# TinyUART.net
KiCad netlist of a schematic drawn in EAGLE
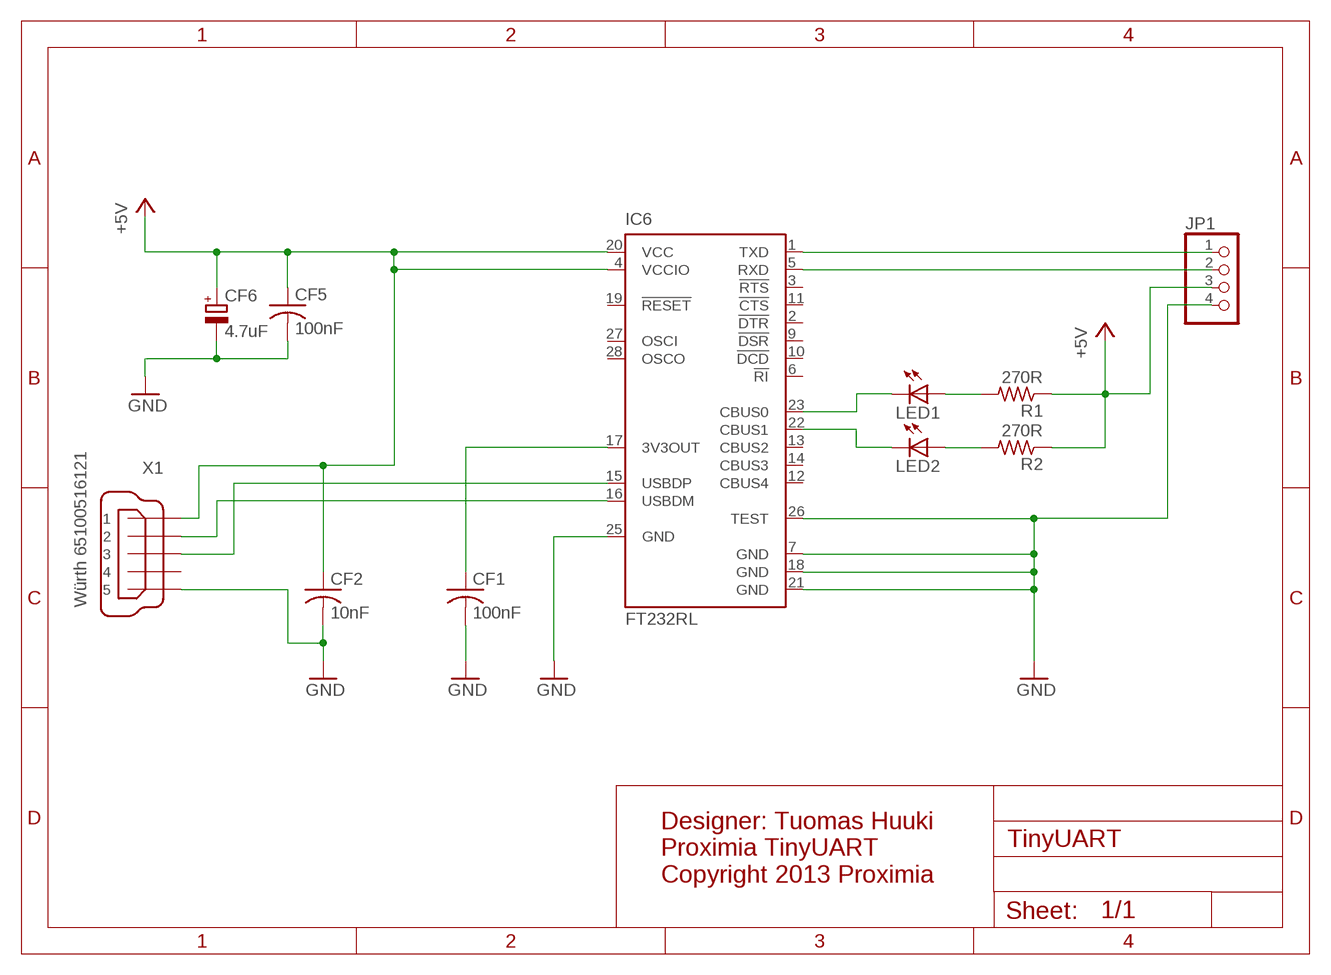
[diagram p0: schematic, sheet 1]

(export (version "E")
  (design (tool "Eeschema 10.0.6"))
  (components
    (comp (ref "CF1")
      (value "100nF")
      (footprint "eagle-import:C0603")
      (libsource (lib "eagle-import") (part "C-USC0603"))
    )
    (comp (ref "CF2")
      (value "10nF")
      (footprint "eagle-import:C0603")
      (libsource (lib "eagle-import") (part "C-USC0603"))
    )
    (comp (ref "CF5")
      (value "100nF")
      (footprint "eagle-import:C0603")
      (libsource (lib "eagle-import") (part "C-USC0603"))
    )
    (comp (ref "CF6")
      (value "4.7uF")
      (footprint "eagle-import:PANASONIC_B")
      (libsource (lib "eagle-import") (part "CPOL-EUB"))
    )
    (comp (ref "IC6")
      (value "FT232RL")
      (footprint "eagle-import:SSOP28")
      (libsource (lib "eagle-import") (part "FT232RL"))
    )
    (comp (ref "JP1")
      (value "PINHD-1X4")
      (footprint "eagle-import:1X04")
      (libsource (lib "eagle-import") (part "PINHD-1X4"))
    )
    (comp (ref "LED1")
      (value "LEDSML1206")
      (footprint "eagle-import:SML1206")
      (libsource (lib "eagle-import") (part "LEDSML1206"))
    )
    (comp (ref "LED2")
      (value "LEDSML1206")
      (footprint "eagle-import:SML1206")
      (libsource (lib "eagle-import") (part "LEDSML1206"))
    )
    (comp (ref "R1")
      (value "270R")
      (footprint "eagle-import:R0603")
      (libsource (lib "eagle-import") (part "R-US_R0603"))
    )
    (comp (ref "R2")
      (value "270R")
      (footprint "eagle-import:R0603")
      (libsource (lib "eagle-import") (part "R-US_R0603"))
    )
    (comp (ref "X1")
      (value "Würth 65100516121")
      (footprint "eagle-import:32005-301")
      (libsource (lib "eagle-import") (part "MINI-USB-32005-301"))
    )
  )
  (nets
    (net (code "1") (name "+5V") (class "Default")
      (node (ref "CF2") (pin "1") (pinfunction "1_1") (pintype "passive"))
      (node (ref "CF5") (pin "1") (pinfunction "1_1") (pintype "passive"))
      (node (ref "CF6") (pin "+") (pinfunction "+_+") (pintype "passive"))
      (node (ref "IC6") (pin "20") (pinfunction "VCC_20") (pintype "power_in"))
      (node (ref "IC6") (pin "4") (pinfunction "VCCIO_4") (pintype "power_in"))
      (node (ref "JP1") (pin "3") (pinfunction "3_3") (pintype "passive"))
      (node (ref "R1") (pin "1") (pinfunction "1_1") (pintype "passive"))
      (node (ref "R2") (pin "1") (pinfunction "1_1") (pintype "passive"))
      (node (ref "X1") (pin "1") (pinfunction "1_1") (pintype "passive"))
    )
    (net (code "2") (name "GND") (class "Default")
      (node (ref "CF1") (pin "2") (pinfunction "2_2") (pintype "passive"))
      (node (ref "CF2") (pin "2") (pinfunction "2_2") (pintype "passive"))
      (node (ref "CF5") (pin "2") (pinfunction "2_2") (pintype "passive"))
      (node (ref "CF6") (pin "-") (pinfunction "-_-") (pintype "passive"))
      (node (ref "IC6") (pin "18") (pinfunction "GND_18") (pintype "power_in"))
      (node (ref "IC6") (pin "21") (pinfunction "GND_21") (pintype "power_in"))
      (node (ref "IC6") (pin "25") (pinfunction "GND_25") (pintype "power_in"))
      (node (ref "IC6") (pin "26") (pinfunction "TEST_26") (pintype "input"))
      (node (ref "IC6") (pin "7") (pinfunction "GND_7") (pintype "power_in"))
      (node (ref "JP1") (pin "4") (pinfunction "4_4") (pintype "passive"))
      (node (ref "X1") (pin "5") (pinfunction "5_5") (pintype "passive"))
    )
    (net (code "3") (name "Net-(IC6-3V3OUT)") (class "Default")
      (node (ref "CF1") (pin "1") (pinfunction "1_1") (pintype "passive"))
      (node (ref "IC6") (pin "17") (pinfunction "3V3OUT_17") (pintype "output"))
    )
    (net (code "4") (name "Net-(IC6-CBUS0)") (class "Default")
      (node (ref "IC6") (pin "23") (pinfunction "CBUS0_23") (pintype "bidirectional"))
      (node (ref "LED1") (pin "C") (pinfunction "C_C") (pintype "passive"))
    )
    (net (code "5") (name "Net-(IC6-CBUS1)") (class "Default")
      (node (ref "IC6") (pin "22") (pinfunction "CBUS1_22") (pintype "bidirectional"))
      (node (ref "LED2") (pin "C") (pinfunction "C_C") (pintype "passive"))
    )
    (net (code "6") (name "Net-(IC6-RXD)") (class "Default")
      (node (ref "IC6") (pin "5") (pinfunction "RXD_5") (pintype "input"))
      (node (ref "JP1") (pin "2") (pinfunction "2_2") (pintype "passive"))
    )
    (net (code "7") (name "Net-(IC6-TXD)") (class "Default")
      (node (ref "IC6") (pin "1") (pinfunction "TXD_1") (pintype "output"))
      (node (ref "JP1") (pin "1") (pinfunction "1_1") (pintype "passive"))
    )
    (net (code "8") (name "Net-(IC6-USBDM)") (class "Default")
      (node (ref "IC6") (pin "16") (pinfunction "USBDM_16") (pintype "bidirectional"))
      (node (ref "X1") (pin "2") (pinfunction "2_2") (pintype "passive"))
    )
    (net (code "9") (name "Net-(IC6-USBDP)") (class "Default")
      (node (ref "IC6") (pin "15") (pinfunction "USBDP_15") (pintype "bidirectional"))
      (node (ref "X1") (pin "3") (pinfunction "3_3") (pintype "passive"))
    )
    (net (code "10") (name "Net-(LED1-PadA)") (class "Default")
      (node (ref "LED1") (pin "A") (pinfunction "A_A") (pintype "passive"))
      (node (ref "R1") (pin "2") (pinfunction "2_2") (pintype "passive"))
    )
    (net (code "11") (name "Net-(LED2-PadA)") (class "Default")
      (node (ref "LED2") (pin "A") (pinfunction "A_A") (pintype "passive"))
      (node (ref "R2") (pin "2") (pinfunction "2_2") (pintype "passive"))
    )
    (net (code "12") (name "unconnected-(IC6-CBUS2-Pad13)") (class "Default")
      (node (ref "IC6") (pin "13") (pinfunction "CBUS2_13") (pintype "bidirectional"))
    )
    (net (code "13") (name "unconnected-(IC6-CBUS3-Pad14)") (class "Default")
      (node (ref "IC6") (pin "14") (pinfunction "CBUS3_14") (pintype "bidirectional"))
    )
    (net (code "14") (name "unconnected-(IC6-CBUS4-Pad12)") (class "Default")
      (node (ref "IC6") (pin "12") (pinfunction "CBUS4_12") (pintype "bidirectional"))
    )
    (net (code "15") (name "unconnected-(IC6-OSCI-Pad27)") (class "Default")
      (node (ref "IC6") (pin "27") (pinfunction "OSCI_27") (pintype "input"))
    )
    (net (code "16") (name "unconnected-(IC6-OSCO-Pad28)") (class "Default")
      (node (ref "IC6") (pin "28") (pinfunction "OSCO_28") (pintype "output"))
    )
    (net (code "17") (name "unconnected-(IC6-~{CTS}-Pad11)") (class "Default")
      (node (ref "IC6") (pin "11") (pinfunction "~{CTS}_11") (pintype "input"))
    )
    (net (code "18") (name "unconnected-(IC6-~{DCD}-Pad10)") (class "Default")
      (node (ref "IC6") (pin "10") (pinfunction "~{DCD}_10") (pintype "input"))
    )
    (net (code "19") (name "unconnected-(IC6-~{DSR}-Pad9)") (class "Default")
      (node (ref "IC6") (pin "9") (pinfunction "~{DSR}_9") (pintype "input"))
    )
    (net (code "20") (name "unconnected-(IC6-~{DTR}-Pad2)") (class "Default")
      (node (ref "IC6") (pin "2") (pinfunction "~{DTR}_2") (pintype "output"))
    )
    (net (code "21") (name "unconnected-(IC6-~{RESET}-Pad19)") (class "Default")
      (node (ref "IC6") (pin "19") (pinfunction "~{RESET}_19") (pintype "input"))
    )
    (net (code "22") (name "unconnected-(IC6-~{RI}-Pad6)") (class "Default")
      (node (ref "IC6") (pin "6") (pinfunction "~{RI}_6") (pintype "input"))
    )
    (net (code "23") (name "unconnected-(IC6-~{RTS}-Pad3)") (class "Default")
      (node (ref "IC6") (pin "3") (pinfunction "~{RTS}_3") (pintype "output"))
    )
    (net (code "24") (name "unconnected-(X1-Pad4)") (class "Default")
      (node (ref "X1") (pin "4") (pinfunction "4_4") (pintype "passive"))
    )
  )
)
